# Sheet1_1.net
KiCad netlist of a schematic drawn in Altium Designer
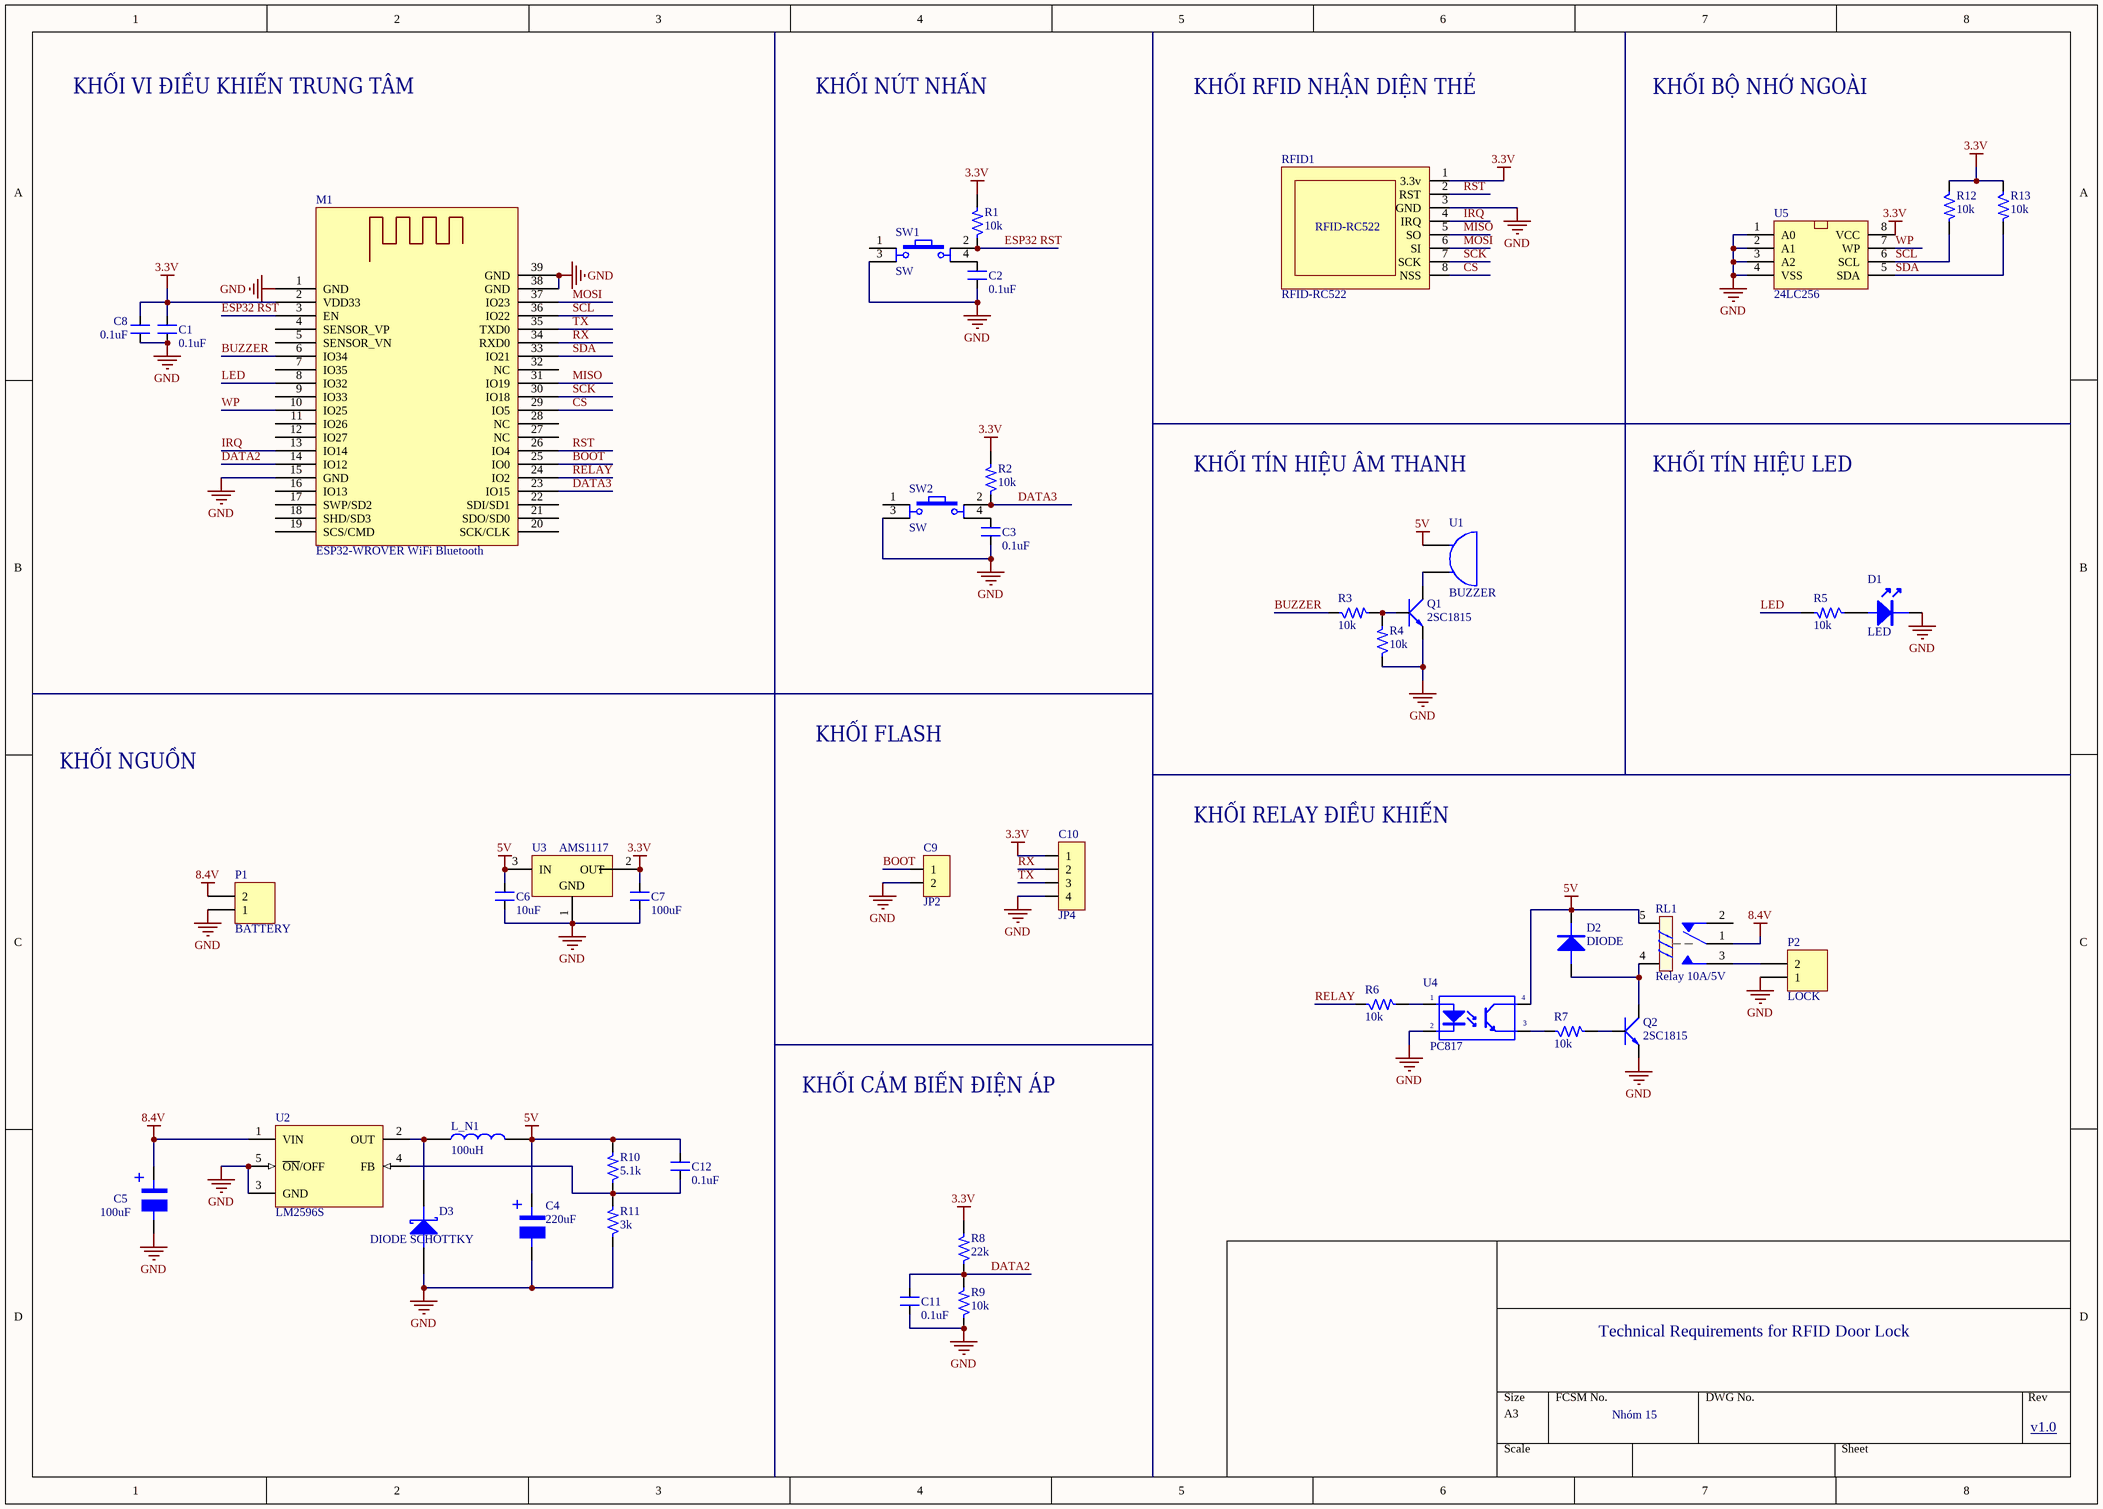
[diagram p0: Sheet1 (1).SchDoc]

(export (version "E")
  (design (tool "Eeschema 10.0.6"))
  (components
    (comp (ref "C1")
      (value "0.1uF")
      (footprint "SMD CAP 0805")
      (description "Cap np W0.4")
      (libsource (lib "KhanhBK_Library_4") (part "CN4"))
    )
    (comp (ref "C2")
      (value "0.1uF")
      (footprint "SMD CAP 0805")
      (description "Cap np W0.4")
      (libsource (lib "KhanhBK_Library_4") (part "CN4"))
    )
    (comp (ref "C3")
      (value "0.1uF")
      (footprint "SMD CAP 0805")
      (description "Cap np W0.4")
      (libsource (lib "KhanhBK_Library_4") (part "CN4"))
    )
    (comp (ref "C4")
      (value "220uF")
      (footprint "Cty1:100UF/16V_SMD")
      (libsource (lib "Devzone_SCHLib") (part "Cap100uF_SMD"))
    )
    (comp (ref "C5")
      (value "100uF")
      (footprint "Cty1:100UF/16V_SMD")
      (libsource (lib "Devzone_SCHLib") (part "Cap100uF_SMD"))
    )
    (comp (ref "C6")
      (value "10uF")
      (footprint "SMD CAP 0805")
      (description "Cap np W0.4")
      (libsource (lib "KhanhBK_Library_4") (part "CN4"))
    )
    (comp (ref "C7")
      (value "100uF")
      (footprint "SMD CAP 0805")
      (description "Cap np W0.4")
      (libsource (lib "KhanhBK_Library_4") (part "CN4"))
    )
    (comp (ref "C8")
      (value "0.1uF")
      (footprint "SMD CAP 0805")
      (description "Cap np W0.4")
      (libsource (lib "KhanhBK_Library_4") (part "CN4"))
    )
    (comp (ref "C9")
      (value "JP2")
      (footprint "JP2-C1T")
      (description "WR-PHD 2.54 mm Angled Socket Header")
      (fields
        (field (name "MANUFACTURER") "Würth Elektronik eiSos GmbH")
        (field (name "PARTNO") "613002143121")
        (field (name "CREATED BY") "Karrer Zheng")
      )
      (libsource (lib "KhanhBK_Library_4") (part "JP2"))
    )
    (comp (ref "C10")
      (value "JP4")
      (footprint "JP4-C1T")
      (description "WR-PHD 2.54 mm Angled Socket Header")
      (fields
        (field (name "MANUFACTURER") "Würth Elektronik eiSos GmbH")
        (field (name "PARTNO") "613004143121")
        (field (name "CREATED BY") "Karrer Zheng")
      )
      (libsource (lib "KhanhBK_Library_4") (part "JP4"))
    )
    (comp (ref "C11")
      (value "0.1uF")
      (footprint "SMD CAP 0805")
      (description "Cap np W0.4")
      (libsource (lib "KhanhBK_Library_4") (part "CN4"))
    )
    (comp (ref "C12")
      (value "0.1uF")
      (footprint "SMD CAP 0805")
      (description "Cap np W0.4")
      (libsource (lib "KhanhBK_Library_4") (part "CN4"))
    )
    (comp (ref "D1") (value "LED") (footprint "CAP10UF") (libsource (lib "Devzone_SCHLib") (part "LED")))
    (comp (ref "D2")
      (value "DIODE")
      (footprint "LL4148 Diode")
      (description "Diode")
      (libsource (lib "Devzone_SCHLib") (part "DIODE"))
    )
    (comp (ref "D3")
      (value "DIODE SCHOTTKY")
      (footprint "SMD SS34")
      (description "Schottky Diode")
      (libsource (lib "Devzone_SCHLib") (part "DIODE SCHOTTKY"))
    )
    (comp (ref "L_N1")
      (value "100uH")
      (footprint "SMD 12mmx8mm Inductor")
      (libsource (lib "Devzone_SCHLib") (part "INDUCTOR1"))
    )
    (comp (ref "M1")
      (value "ESP32-WROVER WiFi Bluetooth")
      (footprint "ESP32-WROOM-32")
      (description "ESP32-WROVER")
      (libsource (lib "KhanhBK_SCH_Lib_5") (part "WIFI_ESP32-WROVER"))
    )
    (comp (ref "P1")
      (value "BATTERY")
      (footprint "CON 2")
      (libsource (lib "KhanhBK_Library_4") (part "HEADER 2"))
    )
    (comp (ref "P2")
      (value "LOCK")
      (footprint "CON 2")
      (libsource (lib "KhanhBK_Library_4") (part "HEADER 2"))
    )
    (comp (ref "Q1")
      (value "2SC1815")
      (footprint "SOT23-321")
      (description "NPN 600mW, ECB")
      (libsource (lib "KhanhBK_Library_4") (part "2SC1815"))
    )
    (comp (ref "Q2")
      (value "2SC1815")
      (footprint "SOT23-321")
      (description "NPN 600mW, ECB")
      (libsource (lib "KhanhBK_Library_4") (part "2SC1815"))
    )
    (comp (ref "R1")
      (value "10k")
      (footprint "SM-0805")
      (description "Resistor 1/4W")
      (libsource (lib "Devzone_SCHLib") (part "Res"))
    )
    (comp (ref "R2")
      (value "10k")
      (footprint "SM-0805")
      (description "Resistor 1/4W")
      (libsource (lib "Devzone_SCHLib") (part "Res"))
    )
    (comp (ref "R3")
      (value "10k")
      (footprint "SM-0805")
      (description "Resistor 1/4W")
      (libsource (lib "Devzone_SCHLib") (part "Res"))
    )
    (comp (ref "R4")
      (value "10k")
      (footprint "SM-0805")
      (description "Resistor 1/4W")
      (libsource (lib "Devzone_SCHLib") (part "Res"))
    )
    (comp (ref "R5")
      (value "10k")
      (footprint "SM-0805")
      (description "Resistor 1/4W")
      (libsource (lib "Devzone_SCHLib") (part "Res"))
    )
    (comp (ref "R6")
      (value "10k")
      (footprint "SM-0805")
      (description "Resistor 1/4W")
      (libsource (lib "Devzone_SCHLib") (part "Res"))
    )
    (comp (ref "R7")
      (value "10k")
      (footprint "SM-0805")
      (description "Resistor 1/4W")
      (libsource (lib "Devzone_SCHLib") (part "Res"))
    )
    (comp (ref "R8")
      (value "22k")
      (footprint "SM-0805")
      (description "Resistor 1/4W")
      (libsource (lib "Devzone_SCHLib") (part "Res"))
    )
    (comp (ref "R9")
      (value "10k")
      (footprint "SM-0805")
      (description "Resistor 1/4W")
      (libsource (lib "Devzone_SCHLib") (part "Res"))
    )
    (comp (ref "R10")
      (value "5.1k")
      (footprint "SM-0805")
      (description "Resistor 1/4W")
      (libsource (lib "Devzone_SCHLib") (part "Res"))
    )
    (comp (ref "R11")
      (value "3k")
      (footprint "SM-0805")
      (description "Resistor 1/4W")
      (libsource (lib "Devzone_SCHLib") (part "Res"))
    )
    (comp (ref "R12")
      (value "10k")
      (footprint "SM-0805")
      (description "Resistor 1/4W")
      (libsource (lib "Devzone_SCHLib") (part "Res"))
    )
    (comp (ref "R13")
      (value "10k")
      (footprint "SM-0805")
      (description "Resistor 1/4W")
      (libsource (lib "Devzone_SCHLib") (part "Res"))
    )
    (comp (ref "RFID1")
      (value "RFID-RC522")
      (footprint "RFID-RC522-BOARD")
      (libsource (lib "SCH_Lib_Devzone") (part "RFID"))
    )
    (comp (ref "RL1")
      (value "Relay 10A/5V")
      (footprint "RL_SPDT_10A")
      (description "Relay SPDT,10A - 12VDC 5 Pin")
      (libsource (lib "KhanhBK_Library_4") (part "Relay 1"))
    )
    (comp (ref "SW1")
      (value "SW")
      (footprint "SW4")
      (description "Switch button 4 pin")
      (libsource (lib "Devzone_SCHLib") (part "SW4"))
    )
    (comp (ref "SW2")
      (value "SW")
      (footprint "SW4")
      (description "Switch button 4 pin")
      (libsource (lib "Devzone_SCHLib") (part "SW4"))
    )
    (comp (ref "U1")
      (value "BUZZER")
      (footprint "BUZZER 5V")
      (description "Buzzer")
      (libsource (lib "Devzone_SCHLib") (part "BUZZER"))
    )
    (comp (ref "U2")
      (value "LM2596S")
      (footprint "TO263-5_Via40/10mil")
      (description "SIMPLE SWITCHER; 3A Step-Down Voltage Regulator")
      (fields
        (field (name "PARTNUMBER") "LM2596S-5.0")
        (field (name "MANUFACTURER") "National Semiconductor")
        (field (name "PUBLISHER") "Altium Limited")
      )
      (libsource (lib "KhanhBK_Library_4") (part "LM2596"))
    )
    (comp (ref "U3")
      (value "AMS1117")
      (footprint "SOT223")
      (libsource (lib "KhanhBK_Library_4") (part "AMS117"))
    )
    (comp (ref "U4")
      (value "PC817")
      (footprint "DIP4/W0.3")
      (description "Single Opto")
      (libsource (lib "Devzone_SCHLib") (part "PC817_1"))
    )
    (comp (ref "U5")
      (value "24LC256")
      (footprint "SOP8_L")
      (description "256KBit I2C CMOS Serial EEPROM")
      (libsource (lib "KhanhBK_SCH_Lib_5") (part "24LC256"))
    )
  )
  (nets
    (net (code "1") (name "/BOOT") (class "Default")
      (node (ref "C9") (pin "1") (pinfunction "1_1") (pintype "passive"))
      (node (ref "M1") (pin "25") (pinfunction "IO0_25") (pintype "passive"))
    )
    (net (code "2") (name "/BUZZER") (class "Default")
      (node (ref "M1") (pin "6") (pinfunction "IO34_6") (pintype "passive"))
      (node (ref "R3") (pin "1") (pinfunction "1_1") (pintype "passive"))
    )
    (net (code "3") (name "/CS") (class "Default")
      (node (ref "M1") (pin "29") (pinfunction "IO5_29") (pintype "passive"))
      (node (ref "RFID1") (pin "8") (pinfunction "NSS_8") (pintype "passive"))
    )
    (net (code "4") (name "/DATA2") (class "Default")
      (node (ref "C11") (pin "2") (pinfunction "2_2") (pintype "passive"))
      (node (ref "M1") (pin "14") (pinfunction "IO12_14") (pintype "passive"))
      (node (ref "R8") (pin "1") (pinfunction "1_1") (pintype "passive"))
      (node (ref "R9") (pin "2") (pinfunction "2_2") (pintype "passive"))
    )
    (net (code "5") (name "/DATA3") (class "Default")
      (node (ref "M1") (pin "23") (pinfunction "IO15_23") (pintype "passive"))
      (node (ref "R2") (pin "1") (pinfunction "1_1") (pintype "passive"))
      (node (ref "SW2") (pin "2") (pintype "passive"))
    )
    (net (code "6") (name "/ESP32 RST") (class "Default")
      (node (ref "M1") (pin "3") (pinfunction "EN_3") (pintype "passive"))
      (node (ref "R1") (pin "1") (pinfunction "1_1") (pintype "passive"))
      (node (ref "SW1") (pin "2") (pintype "passive"))
    )
    (net (code "7") (name "/IRQ") (class "Default")
      (node (ref "M1") (pin "13") (pinfunction "IO14_13") (pintype "passive"))
      (node (ref "RFID1") (pin "4") (pinfunction "IRQ_4") (pintype "passive"))
    )
    (net (code "8") (name "/LED") (class "Default")
      (node (ref "M1") (pin "8") (pinfunction "IO32_8") (pintype "passive"))
      (node (ref "R5") (pin "2") (pinfunction "2_2") (pintype "passive"))
    )
    (net (code "9") (name "/MISO") (class "Default")
      (node (ref "M1") (pin "31") (pinfunction "IO19_31") (pintype "passive"))
      (node (ref "RFID1") (pin "5") (pinfunction "SO_5") (pintype "passive"))
    )
    (net (code "10") (name "/MOSI") (class "Default")
      (node (ref "M1") (pin "37") (pinfunction "IO23_37") (pintype "passive"))
      (node (ref "RFID1") (pin "6") (pinfunction "SI_6") (pintype "passive"))
    )
    (net (code "11") (name "/RELAY") (class "Default")
      (node (ref "M1") (pin "24") (pinfunction "IO2_24") (pintype "passive"))
      (node (ref "R6") (pin "1") (pinfunction "1_1") (pintype "passive"))
    )
    (net (code "12") (name "/RST") (class "Default")
      (node (ref "M1") (pin "26") (pinfunction "IO4_26") (pintype "passive"))
      (node (ref "RFID1") (pin "2") (pinfunction "RST_2") (pintype "passive"))
    )
    (net (code "13") (name "/RX") (class "Default")
      (node (ref "C10") (pin "2") (pinfunction "2_2") (pintype "passive"))
      (node (ref "M1") (pin "34") (pinfunction "RXD0_34") (pintype "passive"))
    )
    (net (code "14") (name "/SCK") (class "Default")
      (node (ref "M1") (pin "30") (pinfunction "IO18_30") (pintype "passive"))
      (node (ref "RFID1") (pin "7") (pinfunction "SCK_7") (pintype "passive"))
    )
    (net (code "15") (name "/SCL") (class "Default")
      (node (ref "M1") (pin "36") (pinfunction "IO22_36") (pintype "passive"))
      (node (ref "R12") (pin "2") (pinfunction "2_2") (pintype "passive"))
      (node (ref "U5") (pin "6") (pinfunction "SCL_6") (pintype "passive"))
    )
    (net (code "16") (name "/SDA") (class "Default")
      (node (ref "M1") (pin "33") (pinfunction "IO21_33") (pintype "passive"))
      (node (ref "R13") (pin "2") (pinfunction "2_2") (pintype "passive"))
      (node (ref "U5") (pin "5") (pinfunction "SDA_5") (pintype "passive"))
    )
    (net (code "17") (name "/TX") (class "Default")
      (node (ref "C10") (pin "3") (pinfunction "3_3") (pintype "passive"))
      (node (ref "M1") (pin "35") (pinfunction "TXD0_35") (pintype "passive"))
    )
    (net (code "18") (name "/WP") (class "Default")
      (node (ref "M1") (pin "10") (pinfunction "IO25_10") (pintype "passive"))
      (node (ref "U5") (pin "7") (pinfunction "WP_7") (pintype "passive"))
    )
    (net (code "19") (name "3.3V") (class "Default")
      (node (ref "C1") (pin "2") (pinfunction "2_2") (pintype "passive"))
      (node (ref "C10") (pin "1") (pinfunction "1_1") (pintype "passive"))
      (node (ref "C7") (pin "2") (pinfunction "2_2") (pintype "passive"))
      (node (ref "C8") (pin "2") (pinfunction "2_2") (pintype "passive"))
      (node (ref "M1") (pin "2") (pinfunction "VDD33_2") (pintype "passive"))
      (node (ref "R1") (pin "2") (pinfunction "2_2") (pintype "passive"))
      (node (ref "R12") (pin "1") (pinfunction "1_1") (pintype "passive"))
      (node (ref "R13") (pin "1") (pinfunction "1_1") (pintype "passive"))
      (node (ref "R2") (pin "2") (pinfunction "2_2") (pintype "passive"))
      (node (ref "R8") (pin "2") (pinfunction "2_2") (pintype "passive"))
      (node (ref "RFID1") (pin "1") (pinfunction "3.3v_1") (pintype "passive"))
      (node (ref "U3") (pin "2") (pinfunction "OUT_2") (pintype "power_in"))
      (node (ref "U3") (pin "4") (pinfunction "4_4") (pintype "passive"))
      (node (ref "U5") (pin "8") (pinfunction "VCC_8") (pintype "passive"))
    )
    (net (code "20") (name "5V") (class "Default")
      (node (ref "C12") (pin "2") (pinfunction "2_2") (pintype "passive"))
      (node (ref "C4") (pin "1") (pinfunction "1_1") (pintype "passive"))
      (node (ref "C6") (pin "2") (pinfunction "2_2") (pintype "passive"))
      (node (ref "D2") (pin "2") (pinfunction "2_2") (pintype "passive"))
      (node (ref "L_N1") (pin "2") (pinfunction "2_2") (pintype "passive"))
      (node (ref "R10") (pin "2") (pinfunction "2_2") (pintype "passive"))
      (node (ref "RL1") (pin "5") (pinfunction "5_5") (pintype "passive"))
      (node (ref "U1") (pin "1") (pinfunction "A_1") (pintype "passive"))
      (node (ref "U3") (pin "3") (pinfunction "IN_3") (pintype "power_in"))
      (node (ref "U4") (pin "4") (pinfunction "C_4") (pintype "passive"))
    )
    (net (code "21") (name "8.4V") (class "Default")
      (node (ref "C5") (pin "1") (pinfunction "1_1") (pintype "passive"))
      (node (ref "P1") (pin "2") (pinfunction "2_2") (pintype "passive"))
      (node (ref "RL1") (pin "1") (pinfunction "1_1") (pintype "passive"))
      (node (ref "U2") (pin "1") (pinfunction "VIN_1") (pintype "power_in"))
    )
    (net (code "22") (name "GND") (class "Default")
      (node (ref "C1") (pin "1") (pinfunction "1_1") (pintype "passive"))
      (node (ref "C10") (pin "4") (pinfunction "4_4") (pintype "passive"))
      (node (ref "C11") (pin "1") (pinfunction "1_1") (pintype "passive"))
      (node (ref "C2") (pin "1") (pinfunction "1_1") (pintype "passive"))
      (node (ref "C3") (pin "1") (pinfunction "1_1") (pintype "passive"))
      (node (ref "C4") (pin "2") (pinfunction "2_2") (pintype "passive"))
      (node (ref "C5") (pin "2") (pinfunction "2_2") (pintype "passive"))
      (node (ref "C6") (pin "1") (pinfunction "1_1") (pintype "passive"))
      (node (ref "C7") (pin "1") (pinfunction "1_1") (pintype "passive"))
      (node (ref "C8") (pin "1") (pinfunction "1_1") (pintype "passive"))
      (node (ref "C9") (pin "2") (pinfunction "2_2") (pintype "passive"))
      (node (ref "D1") (pin "2") (pinfunction "2_2") (pintype "passive"))
      (node (ref "D3") (pin "1") (pinfunction "A_1") (pintype "passive"))
      (node (ref "M1") (pin "1") (pinfunction "GND_1") (pintype "passive"))
      (node (ref "M1") (pin "15") (pinfunction "GND_15") (pintype "passive"))
      (node (ref "M1") (pin "38") (pinfunction "GND_38") (pintype "passive"))
      (node (ref "M1") (pin "39") (pinfunction "GND_39") (pintype "passive"))
      (node (ref "P1") (pin "1") (pinfunction "1_1") (pintype "passive"))
      (node (ref "P2") (pin "1") (pinfunction "1_1") (pintype "passive"))
      (node (ref "Q1") (pin "1") (pinfunction "E_1") (pintype "passive"))
      (node (ref "Q2") (pin "1") (pinfunction "E_1") (pintype "passive"))
      (node (ref "R11") (pin "1") (pinfunction "1_1") (pintype "passive"))
      (node (ref "R4") (pin "1") (pinfunction "1_1") (pintype "passive"))
      (node (ref "R9") (pin "1") (pinfunction "1_1") (pintype "passive"))
      (node (ref "RFID1") (pin "3") (pinfunction "GND_3") (pintype "passive"))
      (node (ref "SW1") (pin "3") (pintype "passive"))
      (node (ref "SW2") (pin "3") (pintype "passive"))
      (node (ref "U2") (pin "3") (pinfunction "GND_3") (pintype "power_in"))
      (node (ref "U2") (pin "5") (pinfunction "~{ON}/OFF_5") (pintype "input"))
      (node (ref "U3") (pin "1") (pinfunction "GND_1") (pintype "power_in"))
      (node (ref "U4") (pin "2") (pinfunction "K_2") (pintype "passive"))
      (node (ref "U5") (pin "1") (pinfunction "A0_1") (pintype "passive"))
      (node (ref "U5") (pin "2") (pinfunction "A1_2") (pintype "passive"))
      (node (ref "U5") (pin "3") (pinfunction "A2_3") (pintype "passive"))
      (node (ref "U5") (pin "4") (pinfunction "VSS_4") (pintype "passive"))
    )
    (net (code "23") (name "Net-(C2-Pad2)") (class "Default")
      (node (ref "C2") (pin "2") (pinfunction "2_2") (pintype "passive"))
      (node (ref "SW1") (pin "4") (pintype "passive"))
    )
    (net (code "24") (name "Net-(C3-Pad2)") (class "Default")
      (node (ref "C3") (pin "2") (pinfunction "2_2") (pintype "passive"))
      (node (ref "SW2") (pin "4") (pintype "passive"))
    )
    (net (code "25") (name "Net-(D1-Pad1)") (class "Default")
      (node (ref "D1") (pin "1") (pinfunction "1_1") (pintype "passive"))
      (node (ref "R5") (pin "1") (pinfunction "1_1") (pintype "passive"))
    )
    (net (code "26") (name "Net-(D3-K)") (class "Default")
      (node (ref "D3") (pin "2") (pinfunction "K_2") (pintype "passive"))
      (node (ref "L_N1") (pin "1") (pinfunction "1_1") (pintype "passive"))
      (node (ref "U2") (pin "2") (pinfunction "OUT_2") (pintype "power_in"))
    )
    (net (code "27") (name "Net-(P2-Pad2)") (class "Default")
      (node (ref "P2") (pin "2") (pinfunction "2_2") (pintype "passive"))
      (node (ref "RL1") (pin "3") (pinfunction "3_3") (pintype "passive"))
    )
    (net (code "28") (name "Net-(Q1-B)") (class "Default")
      (node (ref "Q1") (pin "3") (pinfunction "B_3") (pintype "passive"))
      (node (ref "R3") (pin "2") (pinfunction "2_2") (pintype "passive"))
      (node (ref "R4") (pin "2") (pinfunction "2_2") (pintype "passive"))
    )
    (net (code "29") (name "Net-(Q1-C)") (class "Default")
      (node (ref "Q1") (pin "2") (pinfunction "C_2") (pintype "passive"))
      (node (ref "U1") (pin "2") (pinfunction "B_2") (pintype "passive"))
    )
    (net (code "30") (name "Net-(Q2-B)") (class "Default")
      (node (ref "Q2") (pin "3") (pinfunction "B_3") (pintype "passive"))
      (node (ref "R7") (pin "2") (pinfunction "2_2") (pintype "passive"))
    )
    (net (code "31") (name "Net-(Q2-C)") (class "Default")
      (node (ref "D2") (pin "1") (pinfunction "1_1") (pintype "passive"))
      (node (ref "Q2") (pin "2") (pinfunction "C_2") (pintype "passive"))
      (node (ref "RL1") (pin "4") (pinfunction "4_4") (pintype "passive"))
    )
    (net (code "32") (name "Net-(U2-FB)") (class "Default")
      (node (ref "C12") (pin "1") (pinfunction "1_1") (pintype "passive"))
      (node (ref "R10") (pin "1") (pinfunction "1_1") (pintype "passive"))
      (node (ref "R11") (pin "2") (pinfunction "2_2") (pintype "passive"))
      (node (ref "U2") (pin "4") (pinfunction "FB_4") (pintype "input"))
    )
    (net (code "33") (name "Net-(U4-A)") (class "Default")
      (node (ref "R6") (pin "2") (pinfunction "2_2") (pintype "passive"))
      (node (ref "U4") (pin "1") (pinfunction "A_1") (pintype "passive"))
    )
    (net (code "34") (name "Net-(U4-E)") (class "Default")
      (node (ref "R7") (pin "1") (pinfunction "1_1") (pintype "passive"))
      (node (ref "U4") (pin "3") (pinfunction "E_3") (pintype "passive"))
    )
    (net (code "35") (name "unconnected-(M1-IO13-Pad16)") (class "Default")
      (node (ref "M1") (pin "16") (pinfunction "IO13_16") (pintype "passive"))
    )
    (net (code "36") (name "unconnected-(M1-IO26-Pad11)") (class "Default")
      (node (ref "M1") (pin "11") (pinfunction "IO26_11") (pintype "passive"))
    )
    (net (code "37") (name "unconnected-(M1-IO27-Pad12)") (class "Default")
      (node (ref "M1") (pin "12") (pinfunction "IO27_12") (pintype "passive"))
    )
    (net (code "38") (name "unconnected-(M1-IO33-Pad9)") (class "Default")
      (node (ref "M1") (pin "9") (pinfunction "IO33_9") (pintype "passive"))
    )
    (net (code "39") (name "unconnected-(M1-IO35-Pad7)") (class "Default")
      (node (ref "M1") (pin "7") (pinfunction "IO35_7") (pintype "passive"))
    )
    (net (code "40") (name "unconnected-(M1-NC-Pad27)") (class "Default")
      (node (ref "M1") (pin "27") (pinfunction "NC_27") (pintype "passive"))
    )
    (net (code "41") (name "unconnected-(M1-NC-Pad28)") (class "Default")
      (node (ref "M1") (pin "28") (pinfunction "NC_28") (pintype "passive"))
    )
    (net (code "42") (name "unconnected-(M1-NC-Pad32)") (class "Default")
      (node (ref "M1") (pin "32") (pinfunction "NC_32") (pintype "passive"))
    )
    (net (code "43") (name "unconnected-(M1-SCK{slash}CLK-Pad20)") (class "Default")
      (node (ref "M1") (pin "20") (pinfunction "SCK/CLK_20") (pintype "passive"))
    )
    (net (code "44") (name "unconnected-(M1-SCS{slash}CMD-Pad19)") (class "Default")
      (node (ref "M1") (pin "19") (pinfunction "SCS/CMD_19") (pintype "passive"))
    )
    (net (code "45") (name "unconnected-(M1-SDI{slash}SD1-Pad22)") (class "Default")
      (node (ref "M1") (pin "22") (pinfunction "SDI/SD1_22") (pintype "passive"))
    )
    (net (code "46") (name "unconnected-(M1-SDO{slash}SD0-Pad21)") (class "Default")
      (node (ref "M1") (pin "21") (pinfunction "SDO/SD0_21") (pintype "passive"))
    )
    (net (code "47") (name "unconnected-(M1-SENSOR_VN-Pad5)") (class "Default")
      (node (ref "M1") (pin "5") (pinfunction "SENSOR_VN_5") (pintype "passive"))
    )
    (net (code "48") (name "unconnected-(M1-SENSOR_VP-Pad4)") (class "Default")
      (node (ref "M1") (pin "4") (pinfunction "SENSOR_VP_4") (pintype "passive"))
    )
    (net (code "49") (name "unconnected-(M1-SHD{slash}SD3-Pad18)") (class "Default")
      (node (ref "M1") (pin "18") (pinfunction "SHD/SD3_18") (pintype "passive"))
    )
    (net (code "50") (name "unconnected-(M1-SWP{slash}SD2-Pad17)") (class "Default")
      (node (ref "M1") (pin "17") (pinfunction "SWP/SD2_17") (pintype "passive"))
    )
    (net (code "51") (name "unconnected-(RL1-Pad2)") (class "Default")
      (node (ref "RL1") (pin "2") (pinfunction "2_2") (pintype "passive"))
    )
    (net (code "52") (name "unconnected-(SW1-Pad1)") (class "Default")
      (node (ref "SW1") (pin "1") (pintype "passive"))
    )
    (net (code "53") (name "unconnected-(SW2-Pad1)") (class "Default")
      (node (ref "SW2") (pin "1") (pintype "passive"))
    )
  )
)
